# Lipo_Power.net
KiCad netlist of a schematic drawn in Altium Designer
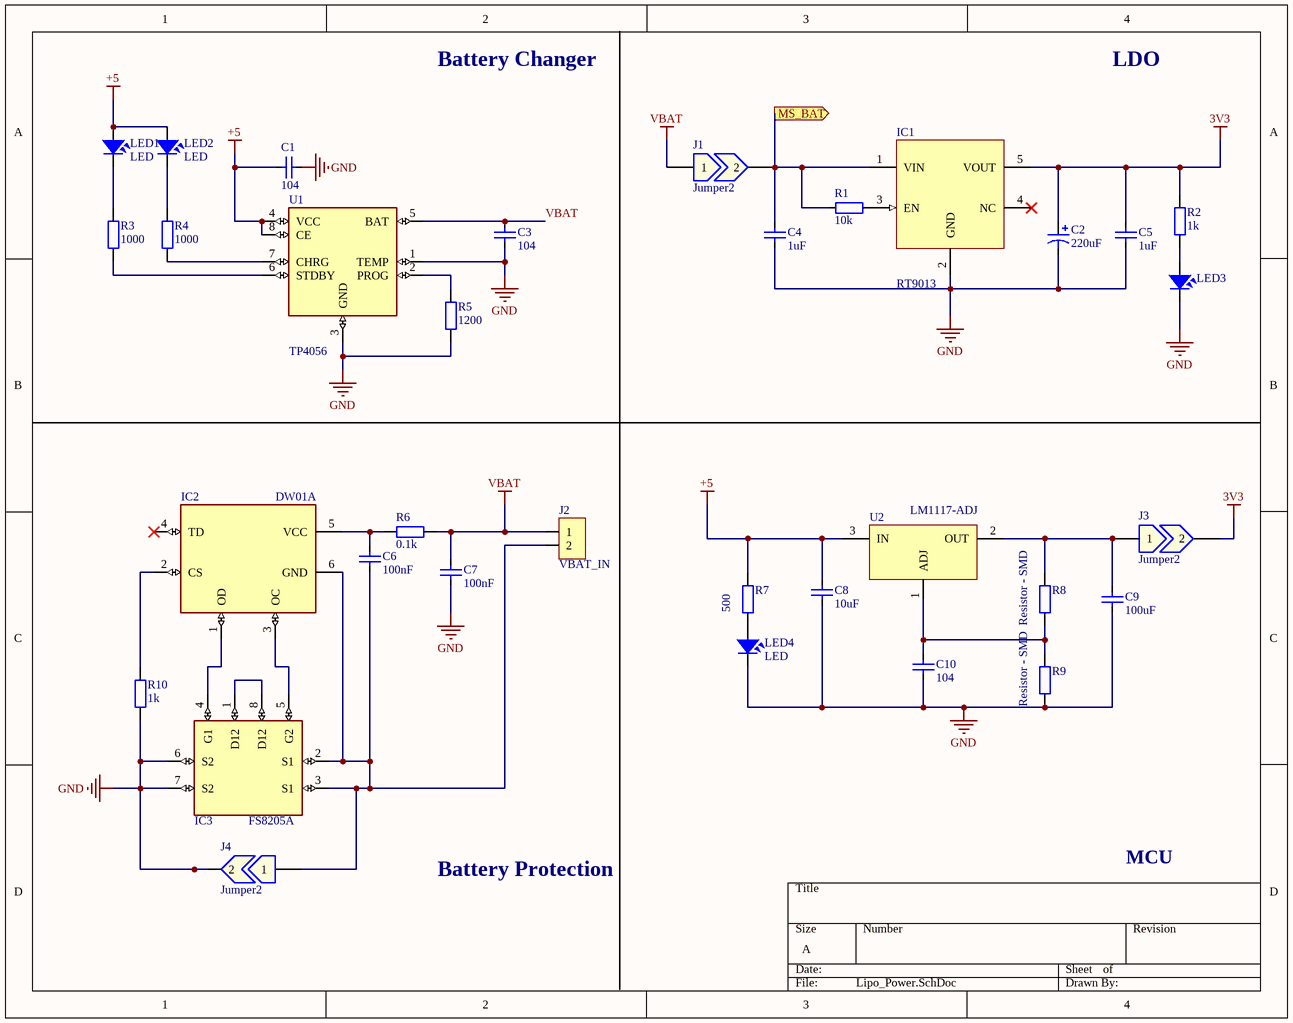
[diagram p0: Lipo_Power.SchDoc]

(export (version "E")
  (design (tool "Eeschema 10.0.6"))
  (components
    (comp (ref "C1")
      (value "104")
      (footprint "CAP_0805")
      (description "Capacitor")
      (fields (field (name "PUBLISHER") "Altium Limited"))
      (libsource (lib "My Library") (part "CapSMD"))
    )
    (comp (ref "C2")
      (value "220uF")
      (footprint "CAP_TANTALUM_3216")
      (description "Polarized Capacitor (Axial)")
      (fields (field (name "PUBLISHER") "Altium Limited"))
      (libsource (lib "My Library") (part "Cap Pol"))
    )
    (comp (ref "C3")
      (value "104")
      (footprint "CAP_0805")
      (description "Capacitor")
      (fields (field (name "PUBLISHER") "Altium Limited"))
      (libsource (lib "My Library") (part "CapSMD"))
    )
    (comp (ref "C4")
      (value "1uF")
      (footprint "CAP_0805")
      (description "Capacitor")
      (fields (field (name "PUBLISHER") "Altium Limited"))
      (libsource (lib "My Library") (part "CapSMD"))
    )
    (comp (ref "C5")
      (value "1uF")
      (footprint "CAP_0805")
      (description "Capacitor")
      (fields (field (name "PUBLISHER") "Altium Limited"))
      (libsource (lib "My Library") (part "CapSMD"))
    )
    (comp (ref "C6")
      (value "100nF")
      (footprint "CAP_0805")
      (description "Capacitor")
      (fields (field (name "PUBLISHER") "Altium Limited"))
      (libsource (lib "My Library") (part "CapSMD"))
    )
    (comp (ref "C7")
      (value "100nF")
      (footprint "CAP_0805")
      (description "Capacitor")
      (fields (field (name "PUBLISHER") "Altium Limited"))
      (libsource (lib "My Library") (part "CapSMD"))
    )
    (comp (ref "C8")
      (value "10uF")
      (footprint "CAP_0805")
      (description "Capacitor")
      (fields (field (name "PUBLISHER") "Altium Limited"))
      (libsource (lib "My Library") (part "CapSMD"))
    )
    (comp (ref "C9")
      (value "100uF")
      (footprint "CAP_0805")
      (description "Capacitor")
      (fields (field (name "PUBLISHER") "Altium Limited"))
      (libsource (lib "My Library") (part "CapSMD"))
    )
    (comp (ref "C10")
      (value "104")
      (footprint "CAP_0805")
      (description "Capacitor")
      (fields (field (name "PUBLISHER") "Altium Limited"))
      (libsource (lib "My Library") (part "CapSMD"))
    )
    (comp (ref "IC1")
      (value "RT9013")
      (footprint "SOT23-5")
      (description "https://linhkien.cxt.vn/5435-rt9013-33gb-ic-reg-linear-33v-500ma-sot23-5.html")
      (libsource (lib "My Library") (part "RT9013"))
    )
    (comp (ref "IC2")
      (value "DW01A")
      (footprint "SOT23-6")
      (description "One Cell Lithium-ion/Polymer Battery Protection IC")
      (libsource (lib "My Library") (part "DW01A"))
    )
    (comp (ref "IC3") (value "FS8205A") (footprint "FS8205A") (libsource (lib "My Library") (part "FS8205A")))
    (comp (ref "J1")
      (value "Jumper2")
      (footprint "JUMPER2")
      (description "Jumper, 2-Pin")
      (libsource (lib "Main") (part "Jumper2"))
    )
    (comp (ref "J2")
      (value "VBAT_IN")
      (footprint "JP2-D1T")
      (description "WR-PHD 2.54 mm Angled Socket Header")
      (fields
        (field (name "MANUFACTURER") "Würth Elektronik eiSos GmbH")
        (field (name "PARTNO") "613002143121")
        (field (name "CREATED BY") "Karrer Zheng")
      )
      (libsource (lib "My Library") (part "JP2"))
    )
    (comp (ref "J3")
      (value "Jumper2")
      (footprint "RES-SMD-0201")
      (description "Jumper, 2-Pin")
      (libsource (lib "My Library") (part "Jumper2"))
    )
    (comp (ref "J4")
      (value "Jumper2")
      (footprint "RES-SMD-0201")
      (description "Jumper, 2-Pin")
      (libsource (lib "My Library") (part "Jumper2"))
    )
    (comp (ref "LED1")
      (value "LED")
      (footprint "LED-0805-Red")
      (description "LED Single colour Green and Red")
      (libsource (lib "My Library") (part "LED"))
    )
    (comp (ref "LED2")
      (value "LED")
      (footprint "LED-0805-Blue")
      (description "LED Single colour Green and Red")
      (libsource (lib "My Library") (part "LED"))
    )
    (comp (ref "LED3")
      (value "~")
      (footprint "LED-0805-Red")
      (description "LED Single colour Green and Red")
      (libsource (lib "Main") (part "LED"))
    )
    (comp (ref "LED4")
      (value "LED")
      (footprint "LED-0805-Red")
      (description "LED Single colour Green and Red")
      (libsource (lib "My Library") (part "LED"))
    )
    (comp (ref "R1")
      (value "10k")
      (footprint "RES-SMD-0805")
      (description "Resistor")
      (fields
        (field (name "MANUFACTURER") "Generic Components")
        (field (name "PUBLISHER") "Altium Hobart Technology Centre")
      )
      (libsource (lib "") (part "Resistor - SMD_1"))
    )
    (comp (ref "R2")
      (value "1k")
      (footprint "RES-SMD-0805")
      (description "Resistor SMD")
      (fields
        (field (name "MANUFACTURER") "Generic Components")
        (field (name "PUBLISHER") "Altium Hobart Technology Centre")
      )
      (libsource (lib "Main") (part "Resistor - SMD"))
    )
    (comp (ref "R3")
      (value "1000")
      (footprint "RES-SMD-0805")
      (description "Resistor SMD")
      (fields
        (field (name "MANUFACTURER") "Generic Components")
        (field (name "PUBLISHER") "Altium Hobart Technology Centre")
      )
      (libsource (lib "My Library") (part "Resistor - SMD"))
    )
    (comp (ref "R4")
      (value "1000")
      (footprint "RES-SMD-0805")
      (description "Resistor SMD")
      (fields
        (field (name "MANUFACTURER") "Generic Components")
        (field (name "PUBLISHER") "Altium Hobart Technology Centre")
      )
      (libsource (lib "My Library") (part "Resistor - SMD"))
    )
    (comp (ref "R5")
      (value "1200")
      (footprint "RES-SMD-0805")
      (description "Resistor SMD")
      (fields
        (field (name "MANUFACTURER") "Generic Components")
        (field (name "PUBLISHER") "Altium Hobart Technology Centre")
      )
      (libsource (lib "My Library") (part "Resistor - SMD"))
    )
    (comp (ref "R6")
      (value "0.1k")
      (footprint "RES-SMD-0805")
      (description "Resistor SMD")
      (fields
        (field (name "MANUFACTURER") "Generic Components")
        (field (name "PUBLISHER") "Altium Hobart Technology Centre")
      )
      (libsource (lib "My Library") (part "Resistor - SMD"))
    )
    (comp (ref "R7")
      (value "500")
      (footprint "RES-SMD-0805")
      (description "Resistor SMD")
      (fields
        (field (name "MANUFACTURER") "Generic Components")
        (field (name "PUBLISHER") "Altium Hobart Technology Centre")
      )
      (libsource (lib "My Library") (part "Resistor - SMD"))
    )
    (comp (ref "R8")
      (value "Resistor - SMD")
      (footprint "RES-SMD-0805")
      (description "Resistor SMD")
      (fields
        (field (name "MANUFACTURER") "Generic Components")
        (field (name "PUBLISHER") "Altium Hobart Technology Centre")
      )
      (libsource (lib "My Library") (part "Resistor - SMD"))
    )
    (comp (ref "R9")
      (value "Resistor - SMD")
      (footprint "RES-SMD-0805")
      (description "Resistor SMD")
      (fields
        (field (name "MANUFACTURER") "Generic Components")
        (field (name "PUBLISHER") "Altium Hobart Technology Centre")
      )
      (libsource (lib "My Library") (part "Resistor - SMD"))
    )
    (comp (ref "R10")
      (value "1k")
      (footprint "RES-SMD-0805")
      (description "Resistor SMD")
      (fields
        (field (name "MANUFACTURER") "Generic Components")
        (field (name "PUBLISHER") "Altium Hobart Technology Centre")
      )
      (libsource (lib "My Library") (part "Resistor - SMD"))
    )
    (comp (ref "U1")
      (value "TP4056")
      (footprint "TP4056")
      (description "Complete single cell Li-Ion battery with a constant current / constant voltage linear charger")
      (libsource (lib "My Library") (part "TP4056"))
    )
    (comp (ref "U2")
      (value "LM1117-ADJ")
      (footprint "LM1117-SOP")
      (description "800mA Low-Dropout Linear Regulator")
      (fields (field (name "CREATOR") "Nguyen Ba Bien"))
      (libsource (lib "My Library") (part "LM1117-ADJ"))
    )
  )
  (nets
    (net (code "1") (name "+5") (class "Default")
      (node (ref "C1") (pin "1") (pinfunction "1_1") (pintype "passive"))
      (node (ref "C8") (pin "1") (pinfunction "1_1") (pintype "passive"))
      (node (ref "LED1") (pin "1") (pinfunction "1_1") (pintype "passive"))
      (node (ref "LED2") (pin "1") (pinfunction "1_1") (pintype "passive"))
      (node (ref "R7") (pin "1") (pinfunction "1_1") (pintype "passive"))
      (node (ref "U1") (pin "4") (pinfunction "VCC_4") (pintype "bidirectional"))
      (node (ref "U1") (pin "8") (pinfunction "CE_8") (pintype "bidirectional"))
      (node (ref "U2") (pin "3") (pinfunction "IN_3") (pintype "passive"))
    )
    (net (code "2") (name "/MS_BAT") (class "Default")
      (node (ref "C4") (pin "1") (pinfunction "1_1") (pintype "passive"))
      (node (ref "IC1") (pin "1") (pinfunction "VIN_1") (pintype "power_in"))
      (node (ref "J1") (pin "2") (pinfunction "2_2") (pintype "passive"))
      (node (ref "R1") (pin "2") (pinfunction "2_2") (pintype "passive"))
    )
    (net (code "3") (name "3V3") (class "Default")
      (node (ref "C2") (pin "1") (pinfunction "1_1") (pintype "passive"))
      (node (ref "C5") (pin "1") (pinfunction "1_1") (pintype "passive"))
      (node (ref "IC1") (pin "5") (pinfunction "VOUT_5") (pintype "power_in"))
      (node (ref "J3") (pin "2") (pinfunction "2_2") (pintype "passive"))
      (node (ref "R2") (pin "2") (pinfunction "2_2") (pintype "passive"))
    )
    (net (code "4") (name "GND") (class "Default")
      (node (ref "C1") (pin "2") (pinfunction "2_2") (pintype "passive"))
      (node (ref "C10") (pin "1") (pinfunction "1_1") (pintype "passive"))
      (node (ref "C2") (pin "2") (pinfunction "2_2") (pintype "passive"))
      (node (ref "C3") (pin "1") (pinfunction "1_1") (pintype "passive"))
      (node (ref "C4") (pin "2") (pinfunction "2_2") (pintype "passive"))
      (node (ref "C5") (pin "2") (pinfunction "2_2") (pintype "passive"))
      (node (ref "C7") (pin "1") (pinfunction "1_1") (pintype "passive"))
      (node (ref "C8") (pin "2") (pinfunction "2_2") (pintype "passive"))
      (node (ref "C9") (pin "1") (pinfunction "1_1") (pintype "passive"))
      (node (ref "IC1") (pin "2") (pinfunction "GND_2") (pintype "power_in"))
      (node (ref "IC3") (pin "6") (pinfunction "S2_6") (pintype "bidirectional"))
      (node (ref "IC3") (pin "7") (pinfunction "S2_7") (pintype "bidirectional"))
      (node (ref "J4") (pin "2") (pinfunction "2_2") (pintype "passive"))
      (node (ref "LED3") (pin "2") (pinfunction "2_2") (pintype "passive"))
      (node (ref "LED4") (pin "2") (pinfunction "2_2") (pintype "passive"))
      (node (ref "R10") (pin "2") (pinfunction "2_2") (pintype "passive"))
      (node (ref "R5") (pin "2") (pinfunction "2_2") (pintype "passive"))
      (node (ref "R9") (pin "2") (pinfunction "2_2") (pintype "passive"))
      (node (ref "U1") (pin "1") (pinfunction "TEMP_1") (pintype "bidirectional"))
      (node (ref "U1") (pin "3") (pinfunction "GND_3") (pintype "bidirectional"))
    )
    (net (code "5") (name "Net-(IC1-EN)") (class "Default")
      (node (ref "IC1") (pin "3") (pinfunction "EN_3") (pintype "input"))
      (node (ref "R1") (pin "1") (pinfunction "1_1") (pintype "passive"))
    )
    (net (code "6") (name "Net-(IC2-CS)") (class "Default")
      (node (ref "IC2") (pin "2") (pinfunction "CS_2") (pintype "bidirectional"))
      (node (ref "R10") (pin "1") (pinfunction "1_1") (pintype "passive"))
    )
    (net (code "7") (name "Net-(IC2-GND)") (class "Default")
      (node (ref "C6") (pin "1") (pinfunction "1_1") (pintype "passive"))
      (node (ref "IC2") (pin "6") (pinfunction "GND_6") (pintype "power_in"))
      (node (ref "IC3") (pin "2") (pinfunction "S1_2") (pintype "bidirectional"))
      (node (ref "IC3") (pin "3") (pinfunction "S1_3") (pintype "bidirectional"))
      (node (ref "J2") (pin "2") (pinfunction "2_2") (pintype "passive"))
      (node (ref "J4") (pin "1") (pinfunction "1_1") (pintype "passive"))
    )
    (net (code "8") (name "Net-(IC2-OC)") (class "Default")
      (node (ref "IC2") (pin "3") (pinfunction "OC_3") (pintype "bidirectional"))
      (node (ref "IC3") (pin "5") (pinfunction "G2_5") (pintype "bidirectional"))
    )
    (net (code "9") (name "Net-(IC2-OD)") (class "Default")
      (node (ref "IC2") (pin "1") (pinfunction "OD_1") (pintype "bidirectional"))
      (node (ref "IC3") (pin "4") (pinfunction "G1_4") (pintype "bidirectional"))
    )
    (net (code "10") (name "Net-(IC2-VCC)") (class "Default")
      (node (ref "C6") (pin "2") (pinfunction "2_2") (pintype "passive"))
      (node (ref "IC2") (pin "5") (pinfunction "VCC_5") (pintype "power_in"))
      (node (ref "R6") (pin "1") (pinfunction "1_1") (pintype "passive"))
    )
    (net (code "11") (name "Net-(IC3-D12-Pad1)") (class "Default")
      (node (ref "IC3") (pin "1") (pinfunction "D12_1") (pintype "bidirectional"))
      (node (ref "IC3") (pin "8") (pinfunction "D12_8") (pintype "bidirectional"))
    )
    (net (code "12") (name "Net-(LED1-Pad2)") (class "Default")
      (node (ref "LED1") (pin "2") (pinfunction "2_2") (pintype "passive"))
      (node (ref "R3") (pin "1") (pinfunction "1_1") (pintype "passive"))
    )
    (net (code "13") (name "Net-(LED2-Pad2)") (class "Default")
      (node (ref "LED2") (pin "2") (pinfunction "2_2") (pintype "passive"))
      (node (ref "R4") (pin "1") (pinfunction "1_1") (pintype "passive"))
    )
    (net (code "14") (name "Net-(LED3-Pad1)") (class "Default")
      (node (ref "LED3") (pin "1") (pinfunction "1_1") (pintype "passive"))
      (node (ref "R2") (pin "1") (pinfunction "1_1") (pintype "passive"))
    )
    (net (code "15") (name "Net-(LED4-Pad1)") (class "Default")
      (node (ref "LED4") (pin "1") (pinfunction "1_1") (pintype "passive"))
      (node (ref "R7") (pin "2") (pinfunction "2_2") (pintype "passive"))
    )
    (net (code "16") (name "Net-(U1-CHRG)") (class "Default")
      (node (ref "R4") (pin "2") (pinfunction "2_2") (pintype "passive"))
      (node (ref "U1") (pin "7") (pinfunction "CHRG_7") (pintype "bidirectional"))
    )
    (net (code "17") (name "Net-(U1-PROG)") (class "Default")
      (node (ref "R5") (pin "1") (pinfunction "1_1") (pintype "passive"))
      (node (ref "U1") (pin "2") (pinfunction "PROG_2") (pintype "bidirectional"))
    )
    (net (code "18") (name "Net-(U1-STDBY)") (class "Default")
      (node (ref "R3") (pin "2") (pinfunction "2_2") (pintype "passive"))
      (node (ref "U1") (pin "6") (pinfunction "STDBY_6") (pintype "bidirectional"))
    )
    (net (code "19") (name "Net-(U2-ADJ)") (class "Default")
      (node (ref "C10") (pin "2") (pinfunction "2_2") (pintype "passive"))
      (node (ref "R8") (pin "2") (pinfunction "2_2") (pintype "passive"))
      (node (ref "R9") (pin "1") (pinfunction "1_1") (pintype "passive"))
      (node (ref "U2") (pin "1") (pinfunction "ADJ_1") (pintype "passive"))
    )
    (net (code "20") (name "Net-(U2-OUT)") (class "Default")
      (node (ref "C9") (pin "2") (pinfunction "2_2") (pintype "passive"))
      (node (ref "J3") (pin "1") (pinfunction "1_1") (pintype "passive"))
      (node (ref "R8") (pin "1") (pinfunction "1_1") (pintype "passive"))
      (node (ref "U2") (pin "2") (pinfunction "OUT_2") (pintype "passive"))
    )
    (net (code "21") (name "VBAT") (class "Default")
      (node (ref "C3") (pin "2") (pinfunction "2_2") (pintype "passive"))
      (node (ref "C7") (pin "2") (pinfunction "2_2") (pintype "passive"))
      (node (ref "J1") (pin "1") (pinfunction "1_1") (pintype "passive"))
      (node (ref "J2") (pin "1") (pinfunction "1_1") (pintype "passive"))
      (node (ref "R6") (pin "2") (pinfunction "2_2") (pintype "passive"))
      (node (ref "U1") (pin "5") (pinfunction "BAT_5") (pintype "bidirectional"))
    )
    (net (code "22") (name "unconnected-(IC1-NC-Pad4)") (class "Default")
      (node (ref "IC1") (pin "4") (pinfunction "NC_4") (pintype "passive+no_connect"))
    )
    (net (code "23") (name "unconnected-(IC2-TD-Pad4)") (class "Default")
      (node (ref "IC2") (pin "4") (pinfunction "TD_4") (pintype "bidirectional+no_connect"))
    )
  )
)
